# POWER.net
KiCad netlist of a schematic drawn in Altium Designer
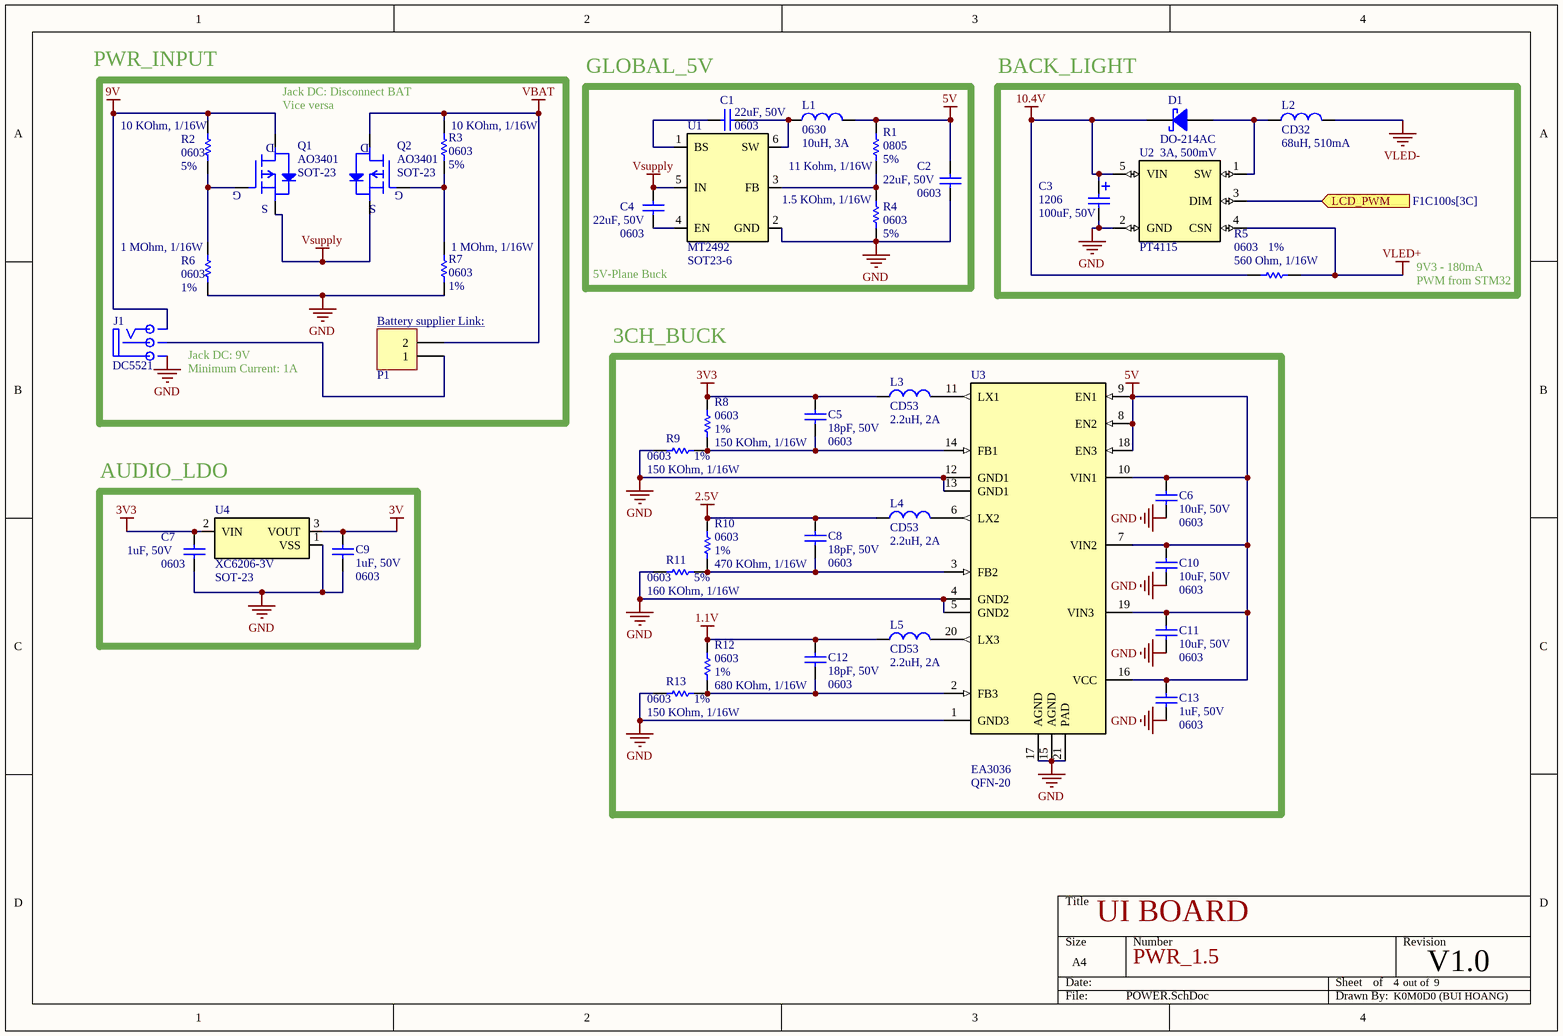
[diagram p0: POWER.SchDoc]

(export (version "E")
  (design (tool "Eeschema 10.0.6"))
  (components
    (comp (ref "C1")
      (value "22uF, 50V")
      (footprint "C_0603")
      (description "CAP_0603")
      (fields (field (name "PACKAGE") "0603"))
      (libsource (lib "DisplayLib") (part "CAP_0603"))
    )
    (comp (ref "C2")
      (value "22uF, 50V")
      (footprint "C_0603")
      (description "CAP_0603")
      (fields (field (name "PACKAGE") "0603"))
      (libsource (lib "DisplayLib") (part "CAP_0603"))
    )
    (comp (ref "C3")
      (value "100uF, 50V")
      (footprint "C_1206+")
      (description "CAP+1206")
      (fields (field (name "PACKAGE") "1206"))
      (libsource (lib "DisplayLib") (part "CAP+1206"))
    )
    (comp (ref "C4")
      (value "22uF, 50V")
      (footprint "C_0603")
      (description "CAP_0603")
      (fields (field (name "PACKAGE") "0603"))
      (libsource (lib "DisplayLib") (part "CAP_0603"))
    )
    (comp (ref "C5")
      (value "18pF, 50V")
      (footprint "C_0603")
      (description "CAP_0603")
      (fields (field (name "PACKAGE") "0603"))
      (libsource (lib "DisplayLib") (part "CAP_0603"))
    )
    (comp (ref "C6")
      (value "10uF, 50V")
      (footprint "C_0603")
      (description "CAP_0603")
      (fields (field (name "PACKAGE") "0603"))
      (libsource (lib "DisplayLib") (part "CAP_0603"))
    )
    (comp (ref "C7")
      (value "1uF, 50V")
      (footprint "C_0603")
      (description "CAP_0603")
      (fields (field (name "PACKAGE") "0603"))
      (libsource (lib "DisplayLib") (part "CAP_0603"))
    )
    (comp (ref "C8")
      (value "18pF, 50V")
      (footprint "C_0603")
      (description "CAP_0603")
      (fields (field (name "PACKAGE") "0603"))
      (libsource (lib "DisplayLib") (part "CAP_0603"))
    )
    (comp (ref "C9")
      (value "1uF, 50V")
      (footprint "C_0603")
      (description "CAP_0603")
      (fields (field (name "PACKAGE") "0603"))
      (libsource (lib "DisplayLib") (part "CAP_0603"))
    )
    (comp (ref "C10")
      (value "10uF, 50V")
      (footprint "C_0603")
      (description "CAP_0603")
      (fields (field (name "PACKAGE") "0603"))
      (libsource (lib "DisplayLib") (part "CAP_0603"))
    )
    (comp (ref "C11")
      (value "10uF, 50V")
      (footprint "C_0603")
      (description "CAP_0603")
      (fields (field (name "PACKAGE") "0603"))
      (libsource (lib "DisplayLib") (part "CAP_0603"))
    )
    (comp (ref "C12")
      (value "18pF, 50V")
      (footprint "C_0603")
      (description "CAP_0603")
      (fields (field (name "PACKAGE") "0603"))
      (libsource (lib "DisplayLib") (part "CAP_0603"))
    )
    (comp (ref "C13")
      (value "1uF, 50V")
      (footprint "C_0603")
      (description "CAP_0603")
      (fields (field (name "PACKAGE") "0603"))
      (libsource (lib "DisplayLib") (part "CAP_0603"))
    )
    (comp (ref "D1")
      (value "3A, 500mV")
      (footprint "PKG_SMA (DO-214AC)")
      (description "SS34")
      (fields (field (name "PACKAGE") "DO-214AC"))
      (libsource (lib "DisplayLib") (part "SCHOTTKY"))
    )
    (comp (ref "J1")
      (value "DC5521")
      (footprint "CONN_DC5521")
      (description "Jack DC")
      (libsource (lib "DisplayLib") (part "DC5521"))
    )
    (comp (ref "L1")
      (value "10uH, 3A")
      (footprint "COIL_74")
      (description "IN_0630")
      (fields (field (name "PACKAGE") "0630"))
      (libsource (lib "DisplayLib") (part "IN_0630"))
    )
    (comp (ref "L2")
      (value "68uH, 510mA")
      (footprint "COIL_CD32")
      (description "IN_CD32")
      (fields (field (name "PACKAGE") "CD32"))
      (libsource (lib "DisplayLib") (part "IN_CD32"))
    )
    (comp (ref "L3")
      (value "2.2uH, 2A")
      (footprint "COIL_CD53")
      (description "IN_CD53")
      (fields (field (name "PACKAGE") "CD53"))
      (libsource (lib "DisplayLib") (part "IN_CD53"))
    )
    (comp (ref "L4")
      (value "2.2uH, 2A")
      (footprint "COIL_CD53")
      (description "IN_CD53")
      (fields (field (name "PACKAGE") "CD53"))
      (libsource (lib "DisplayLib") (part "IN_CD53"))
    )
    (comp (ref "L5")
      (value "2.2uH, 2A")
      (footprint "COIL_CD53")
      (description "IN_CD53")
      (fields (field (name "PACKAGE") "CD53"))
      (libsource (lib "DisplayLib") (part "IN_CD53"))
    )
    (comp (ref "P1")
      (value "Header 2")
      (footprint "JP2")
      (description "Header, 2-Pin")
      (fields (field (name "PUBLISHER") "Altium Limited"))
      (libsource (lib "PIF_Library") (part "Header 2"))
    )
    (comp (ref "Q1")
      (value "AO3401")
      (footprint "PKG_SOT-23")
      (description "P-Channel 30 V 4A (Ta) 1.4W (Ta) Surface Mount SOT-23-3")
      (fields (field (name "PACKAGE") "SOT-23"))
      (libsource (lib "DisplayLib") (part "AO3401"))
    )
    (comp (ref "Q2")
      (value "AO3401")
      (footprint "PKG_SOT-23")
      (description "P-Channel 30 V 4A (Ta) 1.4W (Ta) Surface Mount SOT-23-3")
      (fields (field (name "PACKAGE") "SOT-23"))
      (libsource (lib "DisplayLib") (part "AO3401"))
    )
    (comp (ref "R1")
      (value "11 Kohm, 1/16W")
      (footprint "R_0805")
      (description "RES_0805")
      (fields (field (name "PACKAGE") "0805") (field (name "ACC") "5%"))
      (libsource (lib "DisplayLib") (part "RES_0805"))
    )
    (comp (ref "R2")
      (value "10 KOhm, 1/16W")
      (footprint "R_0603")
      (description "RES_0603")
      (fields (field (name "PACKAGE") "0603") (field (name "ACC") "5%"))
      (libsource (lib "DisplayLib") (part "RES_0603"))
    )
    (comp (ref "R3")
      (value "10 KOhm, 1/16W")
      (footprint "R_0603")
      (description "RES_0603")
      (fields (field (name "PACKAGE") "0603") (field (name "ACC") "5%"))
      (libsource (lib "DisplayLib") (part "RES_0603"))
    )
    (comp (ref "R4")
      (value "1.5 KOhm, 1/16W")
      (footprint "R_0603")
      (description "RES_0603")
      (fields (field (name "PACKAGE") "0603") (field (name "ACC") "5%"))
      (libsource (lib "DisplayLib") (part "RES_0603"))
    )
    (comp (ref "R5")
      (value "560 Ohm, 1/16W")
      (footprint "R_0603")
      (description "RES_0603")
      (fields (field (name "PACKAGE") "0603") (field (name "ACC") "1%"))
      (libsource (lib "DisplayLib") (part "RES_0603"))
    )
    (comp (ref "R6")
      (value "1 MOhm, 1/16W")
      (footprint "R_0603")
      (description "RES_0603")
      (fields (field (name "PACKAGE") "0603") (field (name "ACC") "1%"))
      (libsource (lib "DisplayLib") (part "RES_0603"))
    )
    (comp (ref "R7")
      (value "1 MOhm, 1/16W")
      (footprint "R_0603")
      (description "RES_0603")
      (fields (field (name "PACKAGE") "0603") (field (name "ACC") "1%"))
      (libsource (lib "DisplayLib") (part "RES_0603"))
    )
    (comp (ref "R8")
      (value "150 KOhm, 1/16W")
      (footprint "R_0603")
      (description "RES_0603")
      (fields (field (name "PACKAGE") "0603") (field (name "ACC") "1%"))
      (libsource (lib "DisplayLib") (part "RES_0603"))
    )
    (comp (ref "R9")
      (value "150 KOhm, 1/16W")
      (footprint "R_0603")
      (description "RES_0603")
      (fields (field (name "PACKAGE") "0603") (field (name "ACC") "1%"))
      (libsource (lib "DisplayLib") (part "RES_0603"))
    )
    (comp (ref "R10")
      (value "470 KOhm, 1/16W")
      (footprint "R_0603")
      (description "RES_0603")
      (fields (field (name "PACKAGE") "0603") (field (name "ACC") "1%"))
      (libsource (lib "DisplayLib") (part "RES_0603"))
    )
    (comp (ref "R11")
      (value "160 KOhm, 1/16W")
      (footprint "R_0603")
      (description "RES_0603")
      (fields (field (name "PACKAGE") "0603") (field (name "ACC") "5%"))
      (libsource (lib "DisplayLib") (part "RES_0603"))
    )
    (comp (ref "R12")
      (value "680 KOhm, 1/16W")
      (footprint "R_0603")
      (description "RES_0603")
      (fields (field (name "PACKAGE") "0603") (field (name "ACC") "1%"))
      (libsource (lib "DisplayLib") (part "RES_0603"))
    )
    (comp (ref "R13")
      (value "150 KOhm, 1/16W")
      (footprint "R_0603")
      (description "RES_0603")
      (fields (field (name "PACKAGE") "0603") (field (name "ACC") "1%"))
      (libsource (lib "DisplayLib") (part "RES_0603"))
    )
    (comp (ref "U1")
      (value "MT2492")
      (footprint "PKG-SOT23-6")
      (description "600KHz, 16V，2A Synchronous\r\nStep-Down Converter")
      (fields (field (name "PACKAGE") "SOT23-6"))
      (libsource (lib "DisplayLib") (part "MT2492"))
    )
    (comp (ref "U2")
      (value "PT4115")
      (footprint "PKG_SOT-89-5")
      (description "0V, 1.2A Step-down High Brightness\r\nLED Driver with 5000:1 Dimming")
      (libsource (lib "DisplayLib") (part "PT4115"))
    )
    (comp (ref "U3")
      (value "EA3036")
      (footprint "PKG_QFN-20")
      (description "3CH power management IC for applications powered by one Li-Ion battery or a DC 5V adapter.")
      (fields (field (name "PACKAGE") "QFN-20"))
      (libsource (lib "DisplayLib") (part "EA3036"))
    )
    (comp (ref "U4")
      (value "XC6206-3V")
      (footprint "PKG_SOT-23")
      (description "P-Channel 30 V 4A (Ta) 1.4W (Ta) Surface Mount SOT-23-3")
      (fields (field (name "PACKAGE") "SOT-23"))
      (libsource (lib "DisplayLib") (part "XC6206-2.5V"))
    )
  )
  (nets
    (net (code "1") (name "/LCD_PWM") (class "Default")
      (node (ref "U2") (pin "3") (pinfunction "DIM_3") (pintype "bidirectional"))
    )
    (net (code "2") (name "1.1V") (class "Default")
      (node (ref "C12") (pin "2") (pinfunction "2_2") (pintype "passive"))
      (node (ref "L5") (pin "1") (pinfunction "1_1") (pintype "passive"))
      (node (ref "R12") (pin "2") (pinfunction "2_2") (pintype "passive"))
    )
    (net (code "3") (name "2.5V") (class "Default")
      (node (ref "C8") (pin "2") (pinfunction "2_2") (pintype "passive"))
      (node (ref "L4") (pin "1") (pinfunction "1_1") (pintype "passive"))
      (node (ref "R10") (pin "2") (pinfunction "2_2") (pintype "passive"))
    )
    (net (code "4") (name "3V") (class "Default")
      (node (ref "C9") (pin "2") (pinfunction "2_2") (pintype "passive"))
      (node (ref "U4") (pin "3") (pinfunction "VOUT_3") (pintype "passive"))
    )
    (net (code "5") (name "3V3") (class "Default")
      (node (ref "C5") (pin "2") (pinfunction "2_2") (pintype "passive"))
      (node (ref "C7") (pin "2") (pinfunction "2_2") (pintype "passive"))
      (node (ref "L3") (pin "1") (pinfunction "1_1") (pintype "passive"))
      (node (ref "R8") (pin "2") (pinfunction "2_2") (pintype "passive"))
      (node (ref "U4") (pin "2") (pinfunction "VIN_2") (pintype "passive"))
    )
    (net (code "6") (name "5V") (class "Default")
      (node (ref "C10") (pin "2") (pinfunction "2_2") (pintype "passive"))
      (node (ref "C11") (pin "2") (pinfunction "2_2") (pintype "passive"))
      (node (ref "C13") (pin "2") (pinfunction "2_2") (pintype "passive"))
      (node (ref "C2") (pin "2") (pinfunction "2_2") (pintype "passive"))
      (node (ref "C6") (pin "2") (pinfunction "2_2") (pintype "passive"))
      (node (ref "L1") (pin "2") (pinfunction "2_2") (pintype "passive"))
      (node (ref "R1") (pin "2") (pinfunction "2_2") (pintype "passive"))
      (node (ref "U3") (pin "10") (pinfunction "VIN1_10") (pintype "power_in"))
      (node (ref "U3") (pin "16") (pinfunction "VCC_16") (pintype "power_in"))
      (node (ref "U3") (pin "18") (pinfunction "EN3_18") (pintype "input"))
      (node (ref "U3") (pin "19") (pinfunction "VIN3_19") (pintype "power_in"))
      (node (ref "U3") (pin "7") (pinfunction "VIN2_7") (pintype "power_in"))
      (node (ref "U3") (pin "8") (pinfunction "EN2_8") (pintype "input"))
      (node (ref "U3") (pin "9") (pinfunction "EN1_9") (pintype "input"))
    )
    (net (code "7") (name "9V") (class "Default")
      (node (ref "J1") (pin "1") (pinfunction "DC_1") (pintype "power_in"))
      (node (ref "Q1") (pin "3") (pinfunction "D_3") (pintype "passive"))
      (node (ref "R2") (pin "2") (pinfunction "2_2") (pintype "passive"))
    )
    (net (code "8") (name "10.4V") (class "Default")
      (node (ref "C3") (pin "2") (pinfunction "2_2") (pintype "passive"))
      (node (ref "D1") (pin "1") (pinfunction "K_1") (pintype "passive"))
      (node (ref "R5") (pin "2") (pinfunction "2_2") (pintype "passive"))
      (node (ref "U2") (pin "5") (pinfunction "VIN_5") (pintype "bidirectional"))
    )
    (net (code "9") (name "GND") (class "Default")
      (node (ref "C10") (pin "1") (pinfunction "1_1") (pintype "passive"))
      (node (ref "C11") (pin "1") (pinfunction "1_1") (pintype "passive"))
      (node (ref "C13") (pin "1") (pinfunction "1_1") (pintype "passive"))
      (node (ref "C2") (pin "1") (pinfunction "1_1") (pintype "passive"))
      (node (ref "C3") (pin "1") (pinfunction "1_1") (pintype "passive"))
      (node (ref "C6") (pin "1") (pinfunction "1_1") (pintype "passive"))
      (node (ref "C7") (pin "1") (pinfunction "1_1") (pintype "passive"))
      (node (ref "C9") (pin "1") (pinfunction "1_1") (pintype "passive"))
      (node (ref "J1") (pin "2") (pinfunction "GND_2") (pintype "power_in"))
      (node (ref "R11") (pin "1") (pinfunction "1_1") (pintype "passive"))
      (node (ref "R13") (pin "1") (pinfunction "1_1") (pintype "passive"))
      (node (ref "R4") (pin "1") (pinfunction "1_1") (pintype "passive"))
      (node (ref "R6") (pin "1") (pinfunction "1_1") (pintype "passive"))
      (node (ref "R7") (pin "1") (pinfunction "1_1") (pintype "passive"))
      (node (ref "R9") (pin "1") (pinfunction "1_1") (pintype "passive"))
      (node (ref "U1") (pin "2") (pinfunction "GND_2") (pintype "passive"))
      (node (ref "U2") (pin "2") (pinfunction "GND_2") (pintype "bidirectional"))
      (node (ref "U3") (pin "1") (pinfunction "GND3_1") (pintype "power_in"))
      (node (ref "U3") (pin "12") (pinfunction "GND1_12") (pintype "power_in"))
      (node (ref "U3") (pin "13") (pinfunction "GND1_13") (pintype "power_in"))
      (node (ref "U3") (pin "15") (pinfunction "AGND_15") (pintype "power_in"))
      (node (ref "U3") (pin "17") (pinfunction "AGND_17") (pintype "power_in"))
      (node (ref "U3") (pin "21") (pinfunction "PAD_21") (pintype "power_in"))
      (node (ref "U3") (pin "4") (pinfunction "GND2_4") (pintype "power_in"))
      (node (ref "U3") (pin "5") (pinfunction "GND2_5") (pintype "power_in"))
      (node (ref "U4") (pin "1") (pinfunction "VSS_1") (pintype "power_in"))
    )
    (net (code "10") (name "Net-(D1-A)") (class "Default")
      (node (ref "D1") (pin "2") (pinfunction "A_2") (pintype "passive"))
      (node (ref "L2") (pin "1") (pinfunction "1_1") (pintype "passive"))
      (node (ref "U2") (pin "1") (pinfunction "SW_1") (pintype "bidirectional"))
    )
    (net (code "11") (name "Net-(J1-SW)") (class "Default")
      (node (ref "J1") (pin "3") (pinfunction "SW_3") (pintype "passive"))
      (node (ref "P1") (pin "1") (pinfunction "1_1") (pintype "passive"))
    )
    (net (code "12") (name "Net-(Q1-G)") (class "Default")
      (node (ref "Q1") (pin "1") (pinfunction "G_1") (pintype "passive"))
      (node (ref "R2") (pin "1") (pinfunction "1_1") (pintype "passive"))
      (node (ref "R6") (pin "2") (pinfunction "2_2") (pintype "passive"))
    )
    (net (code "13") (name "Net-(Q2-G)") (class "Default")
      (node (ref "Q2") (pin "1") (pinfunction "G_1") (pintype "passive"))
      (node (ref "R3") (pin "1") (pinfunction "1_1") (pintype "passive"))
      (node (ref "R7") (pin "2") (pinfunction "2_2") (pintype "passive"))
    )
    (net (code "14") (name "Net-(U1-BS)") (class "Default")
      (node (ref "C1") (pin "2") (pinfunction "2_2") (pintype "passive"))
      (node (ref "U1") (pin "1") (pinfunction "BS_1") (pintype "passive"))
    )
    (net (code "15") (name "Net-(U1-EN)") (class "Default")
      (node (ref "C4") (pin "2") (pinfunction "2_2") (pintype "passive"))
      (node (ref "U1") (pin "4") (pinfunction "EN_4") (pintype "passive"))
    )
    (net (code "16") (name "Net-(U1-FB)") (class "Default")
      (node (ref "R1") (pin "1") (pinfunction "1_1") (pintype "passive"))
      (node (ref "R4") (pin "2") (pinfunction "2_2") (pintype "passive"))
      (node (ref "U1") (pin "3") (pinfunction "FB_3") (pintype "passive"))
    )
    (net (code "17") (name "Net-(U1-SW)") (class "Default")
      (node (ref "C1") (pin "1") (pinfunction "1_1") (pintype "passive"))
      (node (ref "L1") (pin "1") (pinfunction "1_1") (pintype "passive"))
      (node (ref "U1") (pin "6") (pinfunction "SW_6") (pintype "passive"))
    )
    (net (code "18") (name "Net-(U3-FB1)") (class "Default")
      (node (ref "C5") (pin "1") (pinfunction "1_1") (pintype "passive"))
      (node (ref "R8") (pin "1") (pinfunction "1_1") (pintype "passive"))
      (node (ref "R9") (pin "2") (pinfunction "2_2") (pintype "passive"))
      (node (ref "U3") (pin "14") (pinfunction "FB1_14") (pintype "input"))
    )
    (net (code "19") (name "Net-(U3-FB2)") (class "Default")
      (node (ref "C8") (pin "1") (pinfunction "1_1") (pintype "passive"))
      (node (ref "R10") (pin "1") (pinfunction "1_1") (pintype "passive"))
      (node (ref "R11") (pin "2") (pinfunction "2_2") (pintype "passive"))
      (node (ref "U3") (pin "3") (pinfunction "FB2_3") (pintype "input"))
    )
    (net (code "20") (name "Net-(U3-FB3)") (class "Default")
      (node (ref "C12") (pin "1") (pinfunction "1_1") (pintype "passive"))
      (node (ref "R12") (pin "1") (pinfunction "1_1") (pintype "passive"))
      (node (ref "R13") (pin "2") (pinfunction "2_2") (pintype "passive"))
      (node (ref "U3") (pin "2") (pinfunction "FB3_2") (pintype "input"))
    )
    (net (code "21") (name "Net-(U3-LX1)") (class "Default")
      (node (ref "L3") (pin "2") (pinfunction "2_2") (pintype "passive"))
      (node (ref "U3") (pin "11") (pinfunction "LX1_11") (pintype "output"))
    )
    (net (code "22") (name "Net-(U3-LX2)") (class "Default")
      (node (ref "L4") (pin "2") (pinfunction "2_2") (pintype "passive"))
      (node (ref "U3") (pin "6") (pinfunction "LX2_6") (pintype "output"))
    )
    (net (code "23") (name "Net-(U3-LX3)") (class "Default")
      (node (ref "L5") (pin "2") (pinfunction "2_2") (pintype "passive"))
      (node (ref "U3") (pin "20") (pinfunction "LX3_20") (pintype "output"))
    )
    (net (code "24") (name "VBAT") (class "Default")
      (node (ref "P1") (pin "2") (pinfunction "2_2") (pintype "passive"))
      (node (ref "Q2") (pin "3") (pinfunction "D_3") (pintype "passive"))
      (node (ref "R3") (pin "2") (pinfunction "2_2") (pintype "passive"))
    )
    (net (code "25") (name "VLED+") (class "Default")
      (node (ref "R5") (pin "1") (pinfunction "1_1") (pintype "passive"))
      (node (ref "U2") (pin "4") (pinfunction "CSN_4") (pintype "bidirectional"))
    )
    (net (code "26") (name "VLED-") (class "Default")
      (node (ref "L2") (pin "2") (pinfunction "2_2") (pintype "passive"))
    )
    (net (code "27") (name "Vsupply") (class "Default")
      (node (ref "C4") (pin "1") (pinfunction "1_1") (pintype "passive"))
      (node (ref "Q1") (pin "2") (pinfunction "S_2") (pintype "passive"))
      (node (ref "Q2") (pin "2") (pinfunction "S_2") (pintype "passive"))
      (node (ref "U1") (pin "5") (pinfunction "IN_5") (pintype "passive"))
    )
  )
)
